# GadgetBox-Mini-Pro-Clone-Modules.net
KiCad netlist of a schematic drawn in EAGLE
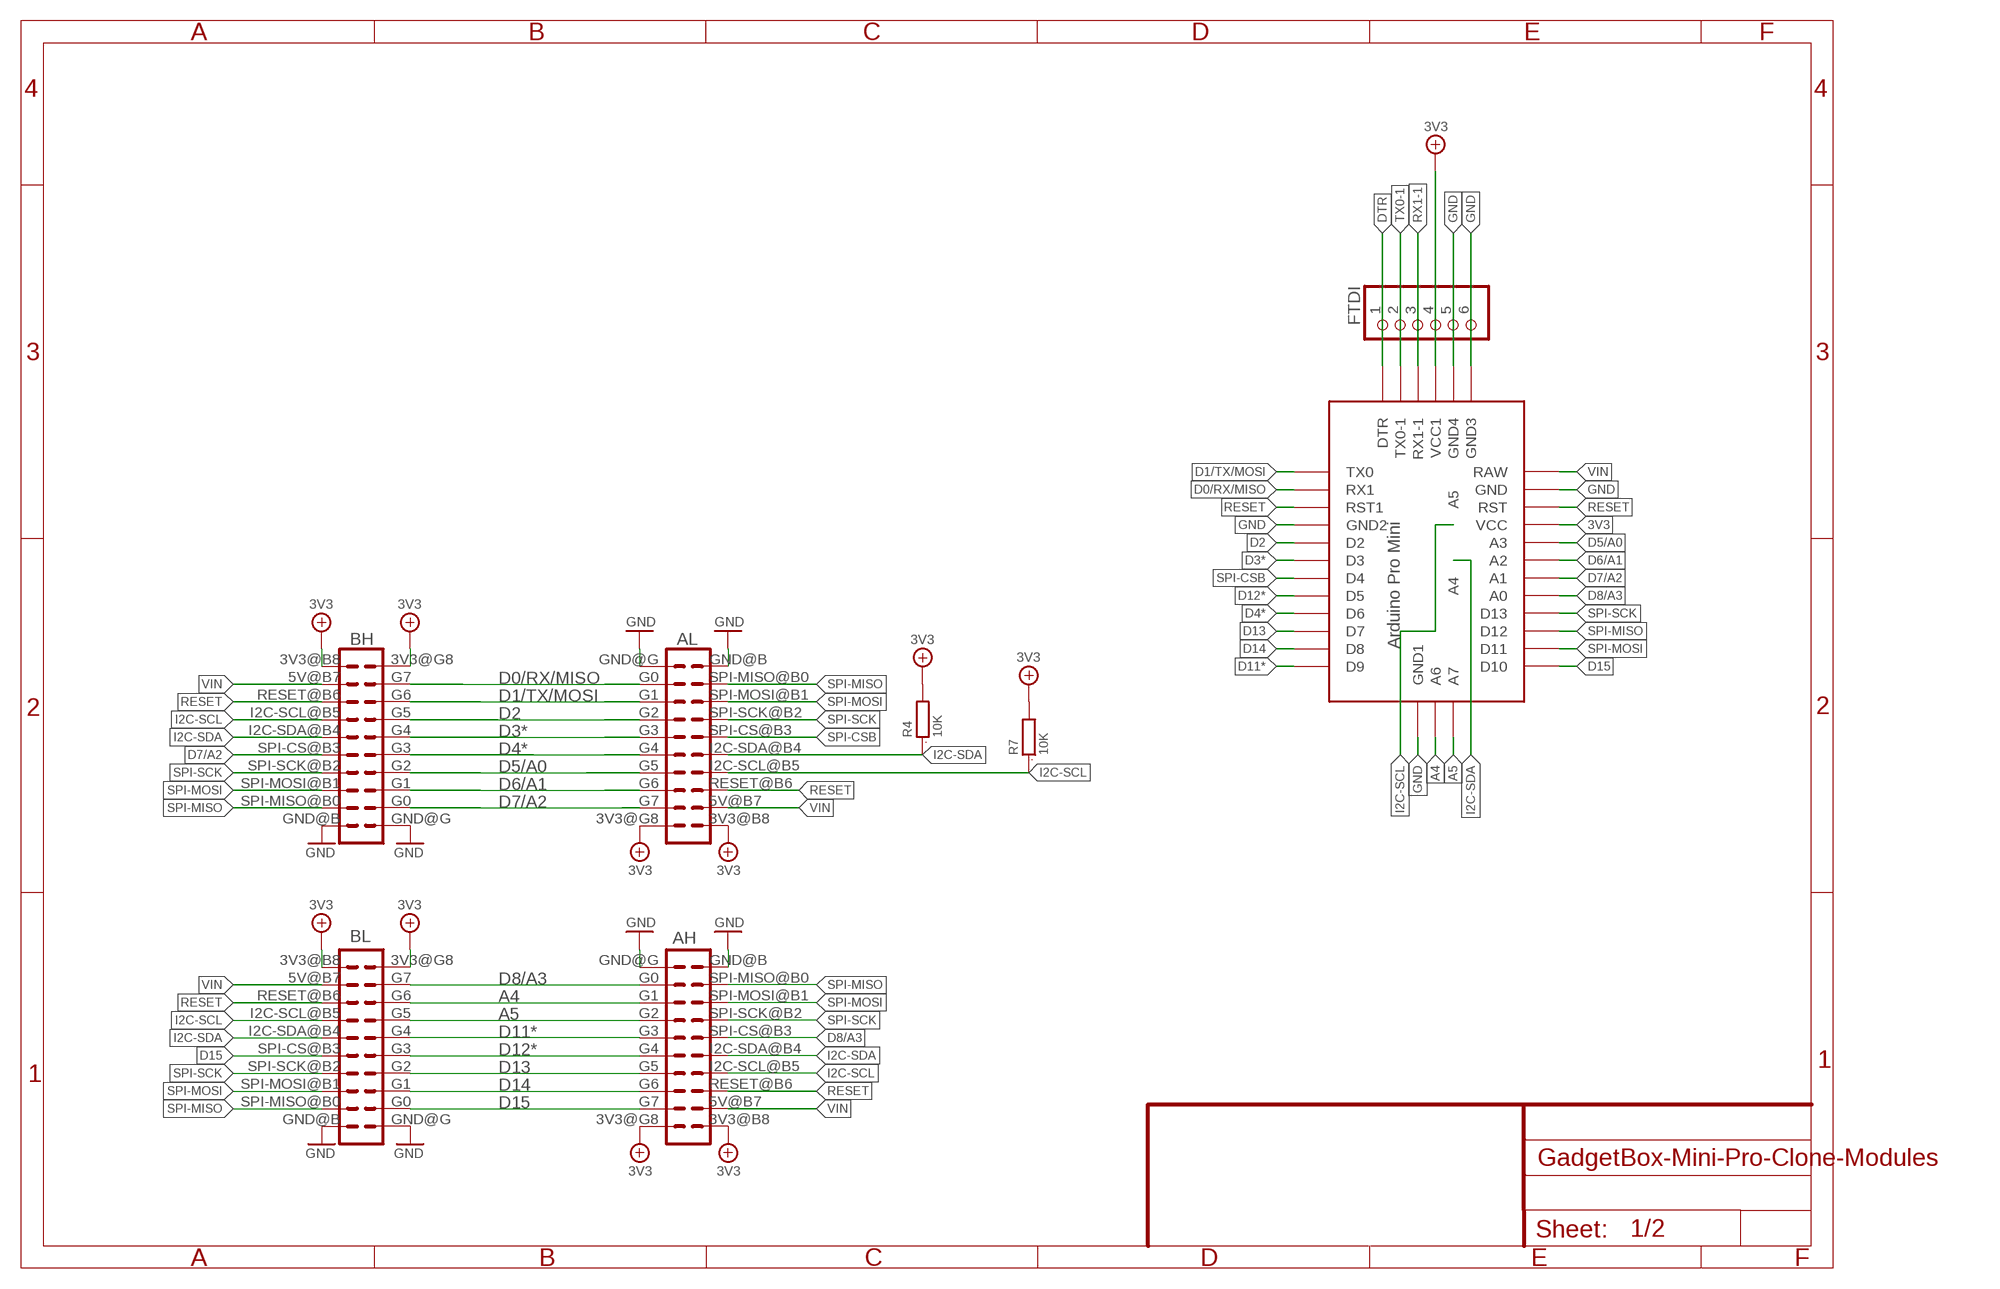
[diagram p0: schematic, sheet 1]
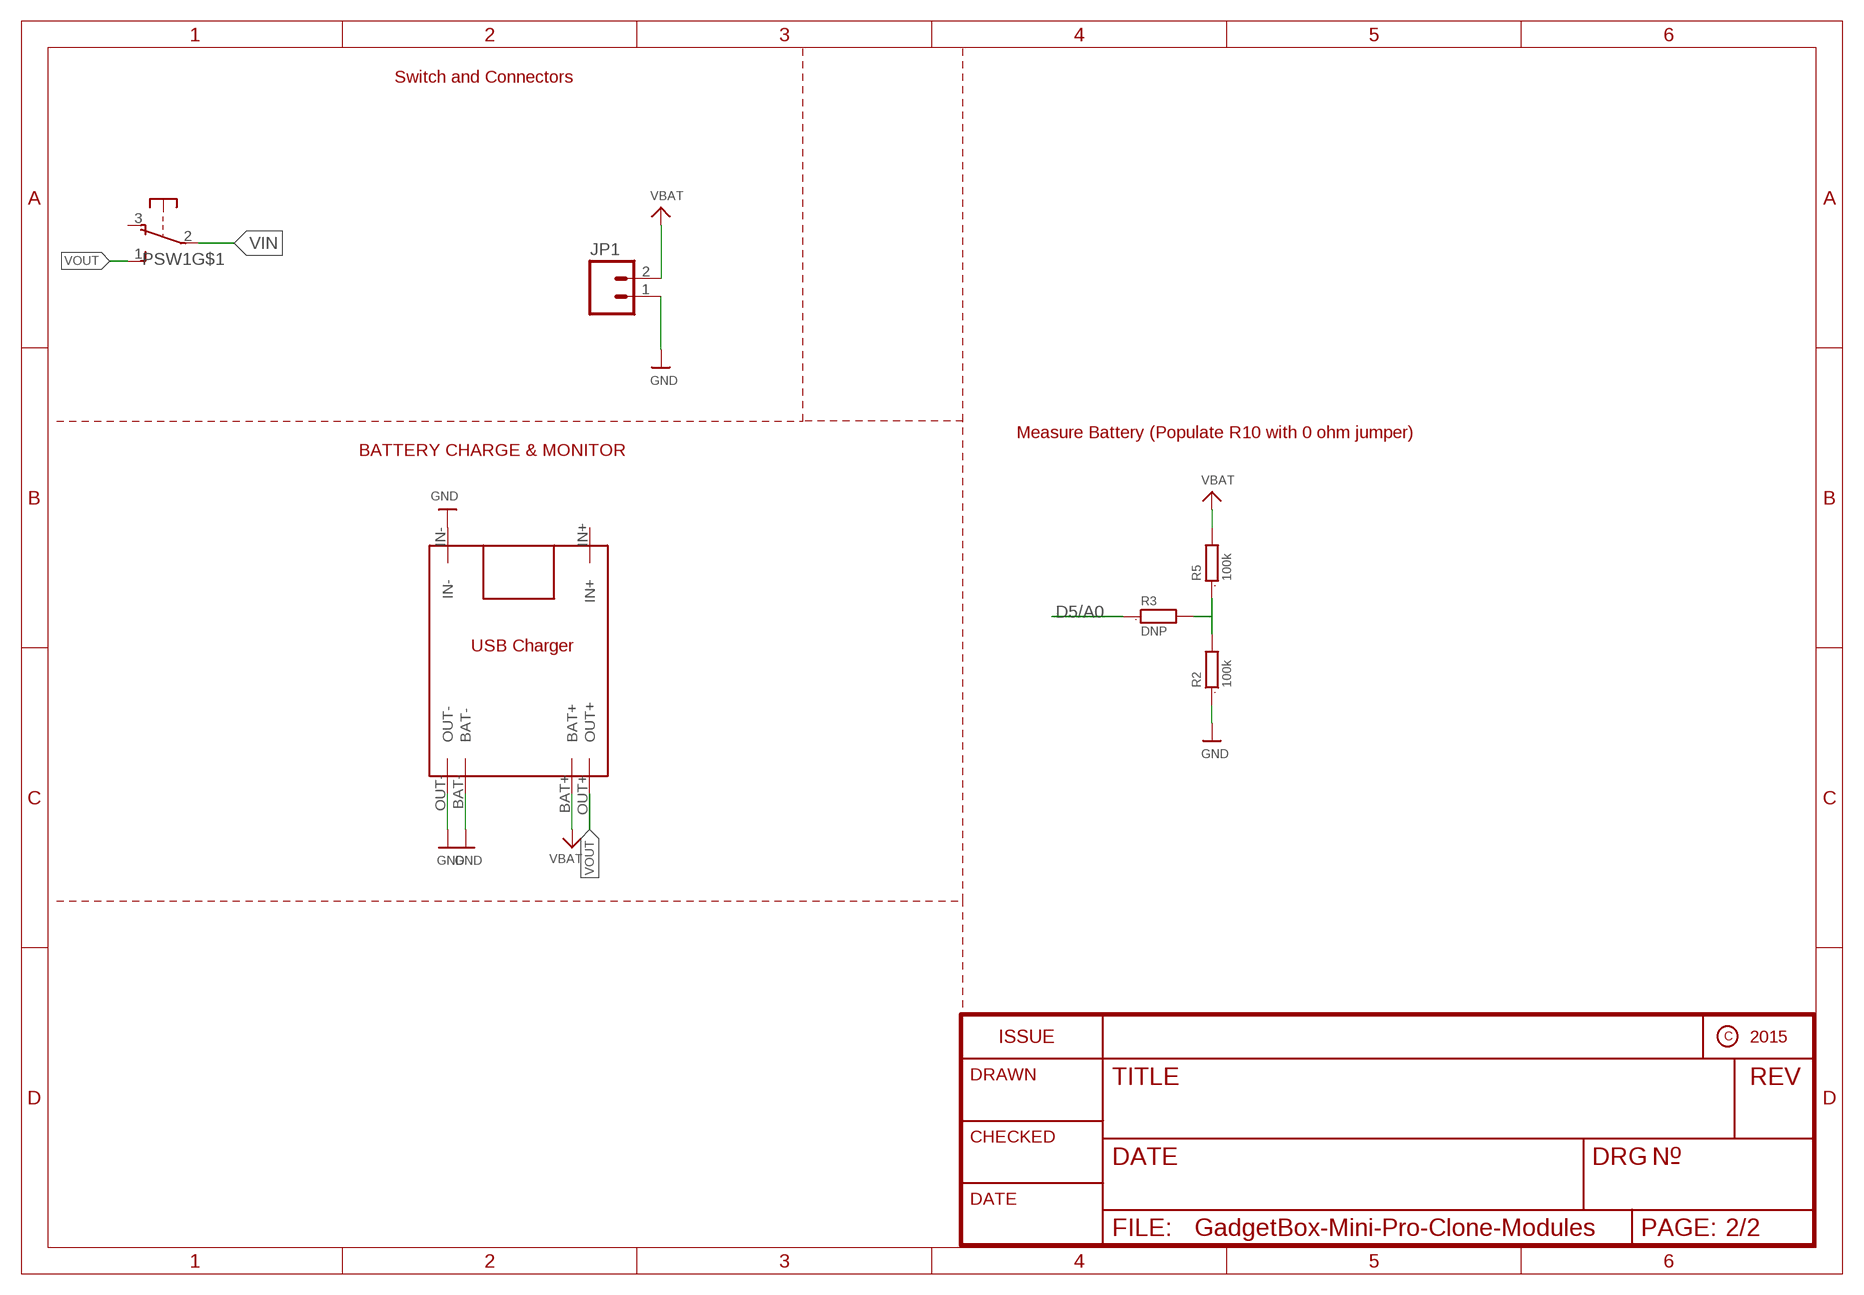
[diagram p1: schematic, sheet 2]

(export (version "E")
  (design (tool "Eeschema 10.0.6"))
  (components
    (comp (ref "AH")
      (value "ECOGECOG_SLOT_ALT1")
      (footprint "eagle-import:ECOG_ALT1")
      (libsource (lib "eagle-import") (part "ECOGECOG_SLOT_ALT1"))
    )
    (comp (ref "AL")
      (value "ECOGECOG_SLOT_ALT1")
      (footprint "eagle-import:ECOG_ALT1")
      (libsource (lib "eagle-import") (part "ECOGECOG_SLOT_ALT1"))
    )
    (comp (ref "BH")
      (value "ECOGECOG_SLOT_ALT1")
      (footprint "eagle-import:ECOG_ALT1")
      (libsource (lib "eagle-import") (part "ECOGECOG_SLOT_ALT1"))
    )
    (comp (ref "BL")
      (value "ECOGECOG_SLOT_ALT1")
      (footprint "eagle-import:ECOG_ALT1")
      (libsource (lib "eagle-import") (part "ECOGECOG_SLOT_ALT1"))
    )
    (comp (ref "FTDI")
      (value "PINHD-1X6")
      (footprint "eagle-import:1X06")
      (libsource (lib "eagle-import") (part "PINHD-1X6"))
    )
    (comp (ref "R4")
      (value "10K")
      (footprint "eagle-import:0603")
      (fields
        (field (name "PARTNO") "RC0603JR-0710KL,YAGEO (VA),dk,311-10KGRCT-ND,RES SMD 10K OHM 5% 1/10W 0603 , REF36")
      )
      (libsource (lib "eagle-import") (part "R0603"))
    )
    (comp (ref "R7")
      (value "10K")
      (footprint "eagle-import:0603")
      (fields
        (field (name "PARTNO") "RC0603JR-0710KL,YAGEO (VA),dk,311-10KGRCT-ND,RES SMD 10K OHM 5% 1/10W 0603 , REF36")
      )
      (libsource (lib "eagle-import") (part "R0603"))
    )
    (comp (ref "U$1")
      (value "ABK-PRO-MINI")
      (footprint "eagle-import:ABK-PRO-MINI")
      (libsource (lib "eagle-import") (part "ABK-PRO-MINI"))
    )
    (comp (ref "JP1")
      (value "M02-JST-2-PTH-NO_SILK")
      (footprint "eagle-import:JST-2-PTH-NS")
      (libsource (lib "eagle-import") (part "M02-JST-2-PTH-NO_SILK"))
    )
    (comp (ref "PSW1")
      (value "OS102011MA1Q")
      (footprint "eagle-import:OS102011MA1Q")
      (fields
        (field (name "PARTNO") "OS102011MA1QN1,C&K Components,dk,CKN9559-ND,SWITCH SLIDE SPDT 100MA 12V , REF72")
      )
      (libsource (lib "eagle-import") (part "OS102011MA1Q"))
    )
    (comp (ref "R2")
      (value "100k")
      (footprint "eagle-import:0603")
      (fields
        (field (name "PARTNO") "RC0603JR-07100KL,YAGEO (VA),dk,311-100KGRCT-ND,RES SMD 100K OHM 5% 1/10W 0603 , REF76")
      )
      (libsource (lib "eagle-import") (part "R0603"))
    )
    (comp (ref "R3")
      (value "DNP")
      (footprint "eagle-import:0603")
      (libsource (lib "eagle-import") (part "R0603"))
    )
    (comp (ref "R5")
      (value "100k")
      (footprint "eagle-import:0603")
      (fields
        (field (name "PARTNO") "RC0603JR-07100KL,YAGEO (VA),dk,311-100KGRCT-ND,RES SMD 100K OHM 5% 1/10W 0603 , REF76")
      )
      (libsource (lib "eagle-import") (part "R0603"))
    )
    (comp (ref "U$5")
      (value "TP4056")
      (footprint "eagle-import:TP4056")
      (libsource (lib "eagle-import") (part "TP4056"))
    )
  )
  (nets
    (net (code "1") (name "3V3") (class "Default")
      (node (ref "AH") (pin "3V3@B8") (pinfunction "3V3_3V3@B8") (pintype "passive"))
      (node (ref "AH") (pin "3V3@G8") (pinfunction "3V3_3V3@G8") (pintype "passive"))
      (node (ref "AL") (pin "3V3@B8") (pinfunction "3V3_3V3@B8") (pintype "passive"))
      (node (ref "AL") (pin "3V3@G8") (pinfunction "3V3_3V3@G8") (pintype "passive"))
      (node (ref "BH") (pin "3V3@B8") (pinfunction "3V3_3V3@B8") (pintype "passive"))
      (node (ref "BH") (pin "3V3@G8") (pinfunction "3V3_3V3@G8") (pintype "passive"))
      (node (ref "BL") (pin "3V3@B8") (pinfunction "3V3_3V3@B8") (pintype "passive"))
      (node (ref "BL") (pin "3V3@G8") (pinfunction "3V3_3V3@G8") (pintype "passive"))
      (node (ref "FTDI") (pin "4") (pinfunction "4_4") (pintype "passive"))
      (node (ref "R4") (pin "2") (pinfunction "2_2") (pintype "passive"))
      (node (ref "R7") (pin "2") (pinfunction "2_2") (pintype "passive"))
      (node (ref "U$1") (pin "VCC") (pinfunction "VCC_VCC") (pintype "bidirectional"))
      (node (ref "U$1") (pin "VCC11") (pinfunction "VCC1_VCC11") (pintype "bidirectional"))
    )
    (net (code "2") (name "A4") (class "Default")
      (node (ref "AH") (pin "G1") (pinfunction "G1_G1") (pintype "passive"))
      (node (ref "BL") (pin "G6") (pinfunction "G6_G6") (pintype "passive"))
      (node (ref "U$1") (pin "A6") (pinfunction "A6_A6") (pintype "bidirectional"))
    )
    (net (code "3") (name "A5") (class "Default")
      (node (ref "AH") (pin "G2") (pinfunction "G2_G2") (pintype "passive"))
      (node (ref "BL") (pin "G5") (pinfunction "G5_G5") (pintype "passive"))
      (node (ref "U$1") (pin "A7") (pinfunction "A7_A7") (pintype "bidirectional"))
    )
    (net (code "4") (name "D0{slash}RX{slash}MISO") (class "Default")
      (node (ref "AL") (pin "G0") (pinfunction "G0_G0") (pintype "passive"))
      (node (ref "BH") (pin "G7") (pinfunction "G7_G7") (pintype "passive"))
      (node (ref "U$1") (pin "RX1") (pinfunction "RX1_RX1") (pintype "bidirectional"))
    )
    (net (code "5") (name "D1{slash}TX{slash}MOSI") (class "Default")
      (node (ref "AL") (pin "G1") (pinfunction "G1_G1") (pintype "passive"))
      (node (ref "BH") (pin "G6") (pinfunction "G6_G6") (pintype "passive"))
      (node (ref "U$1") (pin "TX0") (pinfunction "TX0_TX0") (pintype "bidirectional"))
    )
    (net (code "6") (name "D2") (class "Default")
      (node (ref "AL") (pin "G2") (pinfunction "G2_G2") (pintype "passive"))
      (node (ref "BH") (pin "G5") (pinfunction "G5_G5") (pintype "passive"))
      (node (ref "U$1") (pin "D2") (pinfunction "D2_D2") (pintype "bidirectional"))
    )
    (net (code "7") (name "D3*") (class "Default")
      (node (ref "AL") (pin "G3") (pinfunction "G3_G3") (pintype "passive"))
      (node (ref "BH") (pin "G4") (pinfunction "G4_G4") (pintype "passive"))
      (node (ref "U$1") (pin "D3") (pinfunction "D3_D3") (pintype "bidirectional"))
    )
    (net (code "8") (name "D4*") (class "Default")
      (node (ref "AL") (pin "G4") (pinfunction "G4_G4") (pintype "passive"))
      (node (ref "BH") (pin "G3") (pinfunction "G3_G3") (pintype "passive"))
      (node (ref "U$1") (pin "D6") (pinfunction "D6_D6") (pintype "bidirectional"))
    )
    (net (code "9") (name "D5{slash}A0") (class "Default")
      (node (ref "AL") (pin "G5") (pinfunction "G5_G5") (pintype "passive"))
      (node (ref "BH") (pin "G2") (pinfunction "G2_G2") (pintype "passive"))
      (node (ref "R3") (pin "1") (pinfunction "1_1") (pintype "passive"))
      (node (ref "U$1") (pin "A3") (pinfunction "A3_A3") (pintype "bidirectional"))
    )
    (net (code "10") (name "D6{slash}A1") (class "Default")
      (node (ref "AL") (pin "G6") (pinfunction "G6_G6") (pintype "passive"))
      (node (ref "BH") (pin "G1") (pinfunction "G1_G1") (pintype "passive"))
      (node (ref "U$1") (pin "A2") (pinfunction "A2_A2") (pintype "bidirectional"))
    )
    (net (code "11") (name "D7{slash}A2") (class "Default")
      (node (ref "AL") (pin "G7") (pinfunction "G7_G7") (pintype "passive"))
      (node (ref "BH") (pin "G0") (pinfunction "G0_G0") (pintype "passive"))
      (node (ref "BH") (pin "SPI-CS@B3") (pinfunction "SPI-CS_SPI-CS@B3") (pintype "passive"))
      (node (ref "U$1") (pin "A1") (pinfunction "A1_A1") (pintype "bidirectional"))
    )
    (net (code "12") (name "D8{slash}A3") (class "Default")
      (node (ref "AH") (pin "G0") (pinfunction "G0_G0") (pintype "passive"))
      (node (ref "AH") (pin "SPI-CS@B3") (pinfunction "SPI-CS_SPI-CS@B3") (pintype "passive"))
      (node (ref "BL") (pin "G7") (pinfunction "G7_G7") (pintype "passive"))
      (node (ref "U$1") (pin "A0") (pinfunction "A0_A0") (pintype "bidirectional"))
    )
    (net (code "13") (name "D11*") (class "Default")
      (node (ref "AH") (pin "G3") (pinfunction "G3_G3") (pintype "passive"))
      (node (ref "BL") (pin "G4") (pinfunction "G4_G4") (pintype "passive"))
      (node (ref "U$1") (pin "D9") (pinfunction "D9_D9") (pintype "bidirectional"))
    )
    (net (code "14") (name "D12*") (class "Default")
      (node (ref "AH") (pin "G4") (pinfunction "G4_G4") (pintype "passive"))
      (node (ref "BL") (pin "G3") (pinfunction "G3_G3") (pintype "passive"))
      (node (ref "U$1") (pin "D5") (pinfunction "D5_D5") (pintype "bidirectional"))
    )
    (net (code "15") (name "D13") (class "Default")
      (node (ref "AH") (pin "G5") (pinfunction "G5_G5") (pintype "passive"))
      (node (ref "BL") (pin "G2") (pinfunction "G2_G2") (pintype "passive"))
      (node (ref "U$1") (pin "D7") (pinfunction "D7_D7") (pintype "bidirectional"))
    )
    (net (code "16") (name "D14") (class "Default")
      (node (ref "AH") (pin "G6") (pinfunction "G6_G6") (pintype "passive"))
      (node (ref "BL") (pin "G1") (pinfunction "G1_G1") (pintype "passive"))
      (node (ref "U$1") (pin "D8") (pinfunction "D8_D8") (pintype "bidirectional"))
    )
    (net (code "17") (name "D15") (class "Default")
      (node (ref "AH") (pin "G7") (pinfunction "G7_G7") (pintype "passive"))
      (node (ref "BL") (pin "G0") (pinfunction "G0_G0") (pintype "passive"))
      (node (ref "BL") (pin "SPI-CS@B3") (pinfunction "SPI-CS_SPI-CS@B3") (pintype "passive"))
      (node (ref "U$1") (pin "D10") (pinfunction "D10_D10") (pintype "bidirectional"))
    )
    (net (code "18") (name "DTR") (class "Default")
      (node (ref "FTDI") (pin "1") (pinfunction "1_1") (pintype "passive"))
      (node (ref "U$1") (pin "DTR") (pinfunction "DTR_DTR") (pintype "bidirectional"))
    )
    (net (code "19") (name "GND") (class "Default")
      (node (ref "AH") (pin "GND@B") (pinfunction "GND_GND@B") (pintype "passive"))
      (node (ref "AH") (pin "GND@G") (pinfunction "GND_GND@G") (pintype "passive"))
      (node (ref "AL") (pin "GND@B") (pinfunction "GND_GND@B") (pintype "passive"))
      (node (ref "AL") (pin "GND@G") (pinfunction "GND_GND@G") (pintype "passive"))
      (node (ref "BH") (pin "GND@B") (pinfunction "GND_GND@B") (pintype "passive"))
      (node (ref "BH") (pin "GND@G") (pinfunction "GND_GND@G") (pintype "passive"))
      (node (ref "BL") (pin "GND@B") (pinfunction "GND_GND@B") (pintype "passive"))
      (node (ref "BL") (pin "GND@G") (pinfunction "GND_GND@G") (pintype "passive"))
      (node (ref "FTDI") (pin "5") (pinfunction "5_5") (pintype "passive"))
      (node (ref "FTDI") (pin "6") (pinfunction "6_6") (pintype "passive"))
      (node (ref "JP1") (pin "1") (pinfunction "1_1") (pintype "passive"))
      (node (ref "R2") (pin "1") (pinfunction "1_1") (pintype "passive"))
      (node (ref "U$1") (pin "GND") (pinfunction "GND_GND") (pintype "bidirectional"))
      (node (ref "U$1") (pin "GND1") (pinfunction "GND1_GND1") (pintype "bidirectional"))
      (node (ref "U$1") (pin "GND2") (pinfunction "GND2_GND2") (pintype "bidirectional"))
      (node (ref "U$1") (pin "GND3") (pinfunction "GND3_GND3") (pintype "bidirectional"))
      (node (ref "U$1") (pin "GND4") (pinfunction "GND4_GND4") (pintype "bidirectional"))
      (node (ref "U$5") (pin "BAT-") (pinfunction "BAT-_BAT-") (pintype "bidirectional"))
      (node (ref "U$5") (pin "IN-") (pinfunction "IN-_IN-") (pintype "bidirectional"))
      (node (ref "U$5") (pin "OUT-") (pinfunction "OUT-_OUT-") (pintype "bidirectional"))
    )
    (net (code "20") (name "I2C-SCL") (class "Default")
      (node (ref "AH") (pin "I2C-SCL@B5") (pinfunction "I2C-SCL_I2C-SCL@B5") (pintype "passive"))
      (node (ref "AL") (pin "I2C-SCL@B5") (pinfunction "I2C-SCL_I2C-SCL@B5") (pintype "passive"))
      (node (ref "BH") (pin "I2C-SCL@B5") (pinfunction "I2C-SCL_I2C-SCL@B5") (pintype "passive"))
      (node (ref "BL") (pin "I2C-SCL@B5") (pinfunction "I2C-SCL_I2C-SCL@B5") (pintype "passive"))
      (node (ref "R7") (pin "1") (pinfunction "1_1") (pintype "passive"))
      (node (ref "U$1") (pin "A5") (pinfunction "A5_A5") (pintype "bidirectional"))
    )
    (net (code "21") (name "I2C-SDA") (class "Default")
      (node (ref "AH") (pin "I2C-SDA@B4") (pinfunction "I2C-SDA_I2C-SDA@B4") (pintype "passive"))
      (node (ref "AL") (pin "I2C-SDA@B4") (pinfunction "I2C-SDA_I2C-SDA@B4") (pintype "passive"))
      (node (ref "BH") (pin "I2C-SDA@B4") (pinfunction "I2C-SDA_I2C-SDA@B4") (pintype "passive"))
      (node (ref "BL") (pin "I2C-SDA@B4") (pinfunction "I2C-SDA_I2C-SDA@B4") (pintype "passive"))
      (node (ref "R4") (pin "1") (pinfunction "1_1") (pintype "passive"))
      (node (ref "U$1") (pin "A4") (pinfunction "A4_A4") (pintype "bidirectional"))
    )
    (net (code "22") (name "Net-(R2-Pad2)") (class "Default")
      (node (ref "R2") (pin "2") (pinfunction "2_2") (pintype "passive"))
      (node (ref "R3") (pin "2") (pinfunction "2_2") (pintype "passive"))
      (node (ref "R5") (pin "1") (pinfunction "1_1") (pintype "passive"))
    )
    (net (code "23") (name "RESET") (class "Default")
      (node (ref "AH") (pin "RESET@B6") (pinfunction "RESET_RESET@B6") (pintype "passive"))
      (node (ref "AL") (pin "RESET@B6") (pinfunction "RESET_RESET@B6") (pintype "passive"))
      (node (ref "BH") (pin "RESET@B6") (pinfunction "RESET_RESET@B6") (pintype "passive"))
      (node (ref "BL") (pin "RESET@B6") (pinfunction "RESET_RESET@B6") (pintype "passive"))
      (node (ref "U$1") (pin "RST") (pinfunction "RST_RST") (pintype "bidirectional"))
      (node (ref "U$1") (pin "RST1") (pinfunction "RST1_RST1") (pintype "bidirectional"))
    )
    (net (code "24") (name "RX1-1") (class "Default")
      (node (ref "FTDI") (pin "3") (pinfunction "3_3") (pintype "passive"))
      (node (ref "U$1") (pin "RX1-1") (pinfunction "RX1-1_RX1-1") (pintype "bidirectional"))
    )
    (net (code "25") (name "SPI-CSB") (class "Default")
      (node (ref "AL") (pin "SPI-CS@B3") (pinfunction "SPI-CS_SPI-CS@B3") (pintype "passive"))
      (node (ref "U$1") (pin "D4") (pinfunction "D4_D4") (pintype "bidirectional"))
    )
    (net (code "26") (name "SPI-MISO") (class "Default")
      (node (ref "AH") (pin "SPI-MISO@B0") (pinfunction "SPI-MISO_SPI-MISO@B0") (pintype "passive"))
      (node (ref "AL") (pin "SPI-MISO@B0") (pinfunction "SPI-MISO_SPI-MISO@B0") (pintype "passive"))
      (node (ref "BH") (pin "SPI-MISO@B0") (pinfunction "SPI-MISO_SPI-MISO@B0") (pintype "passive"))
      (node (ref "BL") (pin "SPI-MISO@B0") (pinfunction "SPI-MISO_SPI-MISO@B0") (pintype "passive"))
      (node (ref "U$1") (pin "D12") (pinfunction "D12_D12") (pintype "bidirectional"))
    )
    (net (code "27") (name "SPI-MOSI") (class "Default")
      (node (ref "AH") (pin "SPI-MOSI@B1") (pinfunction "SPI-MOSI_SPI-MOSI@B1") (pintype "passive"))
      (node (ref "AL") (pin "SPI-MOSI@B1") (pinfunction "SPI-MOSI_SPI-MOSI@B1") (pintype "passive"))
      (node (ref "BH") (pin "SPI-MOSI@B1") (pinfunction "SPI-MOSI_SPI-MOSI@B1") (pintype "passive"))
      (node (ref "BL") (pin "SPI-MOSI@B1") (pinfunction "SPI-MOSI_SPI-MOSI@B1") (pintype "passive"))
      (node (ref "U$1") (pin "D11") (pinfunction "D11_D11") (pintype "bidirectional"))
    )
    (net (code "28") (name "SPI-SCK") (class "Default")
      (node (ref "AH") (pin "SPI-SCK@B2") (pinfunction "SPI-SCK_SPI-SCK@B2") (pintype "passive"))
      (node (ref "AL") (pin "SPI-SCK@B2") (pinfunction "SPI-SCK_SPI-SCK@B2") (pintype "passive"))
      (node (ref "BH") (pin "SPI-SCK@B2") (pinfunction "SPI-SCK_SPI-SCK@B2") (pintype "passive"))
      (node (ref "BL") (pin "SPI-SCK@B2") (pinfunction "SPI-SCK_SPI-SCK@B2") (pintype "passive"))
      (node (ref "U$1") (pin "D13") (pinfunction "D13_D13") (pintype "bidirectional"))
    )
    (net (code "29") (name "TX0-1") (class "Default")
      (node (ref "FTDI") (pin "2") (pinfunction "2_2") (pintype "passive"))
      (node (ref "U$1") (pin "TX0-1") (pinfunction "TX0-1_TX0-1") (pintype "bidirectional"))
    )
    (net (code "30") (name "VBAT") (class "Default")
      (node (ref "JP1") (pin "2") (pinfunction "2_2") (pintype "passive"))
      (node (ref "R5") (pin "2") (pinfunction "2_2") (pintype "passive"))
      (node (ref "U$5") (pin "BAT+") (pinfunction "BAT+_BAT+") (pintype "bidirectional"))
    )
    (net (code "31") (name "VIN") (class "Default")
      (node (ref "AH") (pin "5V@B7") (pinfunction "5V_5V@B7") (pintype "passive"))
      (node (ref "AL") (pin "5V@B7") (pinfunction "5V_5V@B7") (pintype "passive"))
      (node (ref "BH") (pin "5V@B7") (pinfunction "5V_5V@B7") (pintype "passive"))
      (node (ref "BL") (pin "5V@B7") (pinfunction "5V_5V@B7") (pintype "passive"))
      (node (ref "PSW1") (pin "2") (pinfunction "P_2") (pintype "passive"))
      (node (ref "U$1") (pin "RAW") (pinfunction "RAW_RAW") (pintype "bidirectional"))
    )
    (net (code "32") (name "VOUT") (class "Default")
      (node (ref "PSW1") (pin "1") (pinfunction "S_1") (pintype "passive"))
      (node (ref "U$5") (pin "OUT+") (pinfunction "OUT+_OUT+") (pintype "bidirectional"))
    )
    (net (code "33") (name "unconnected-(PSW1A-O-Pad3)") (class "Default")
      (node (ref "PSW1") (pin "3") (pinfunction "O_3") (pintype "passive"))
    )
    (net (code "34") (name "unconnected-(U$5-PadIN+)") (class "Default")
      (node (ref "U$5") (pin "IN+") (pinfunction "IN+_IN+") (pintype "bidirectional"))
    )
  )
)
